# Indicators_Buttons.net
KiCad netlist of a schematic drawn in Altium Designer
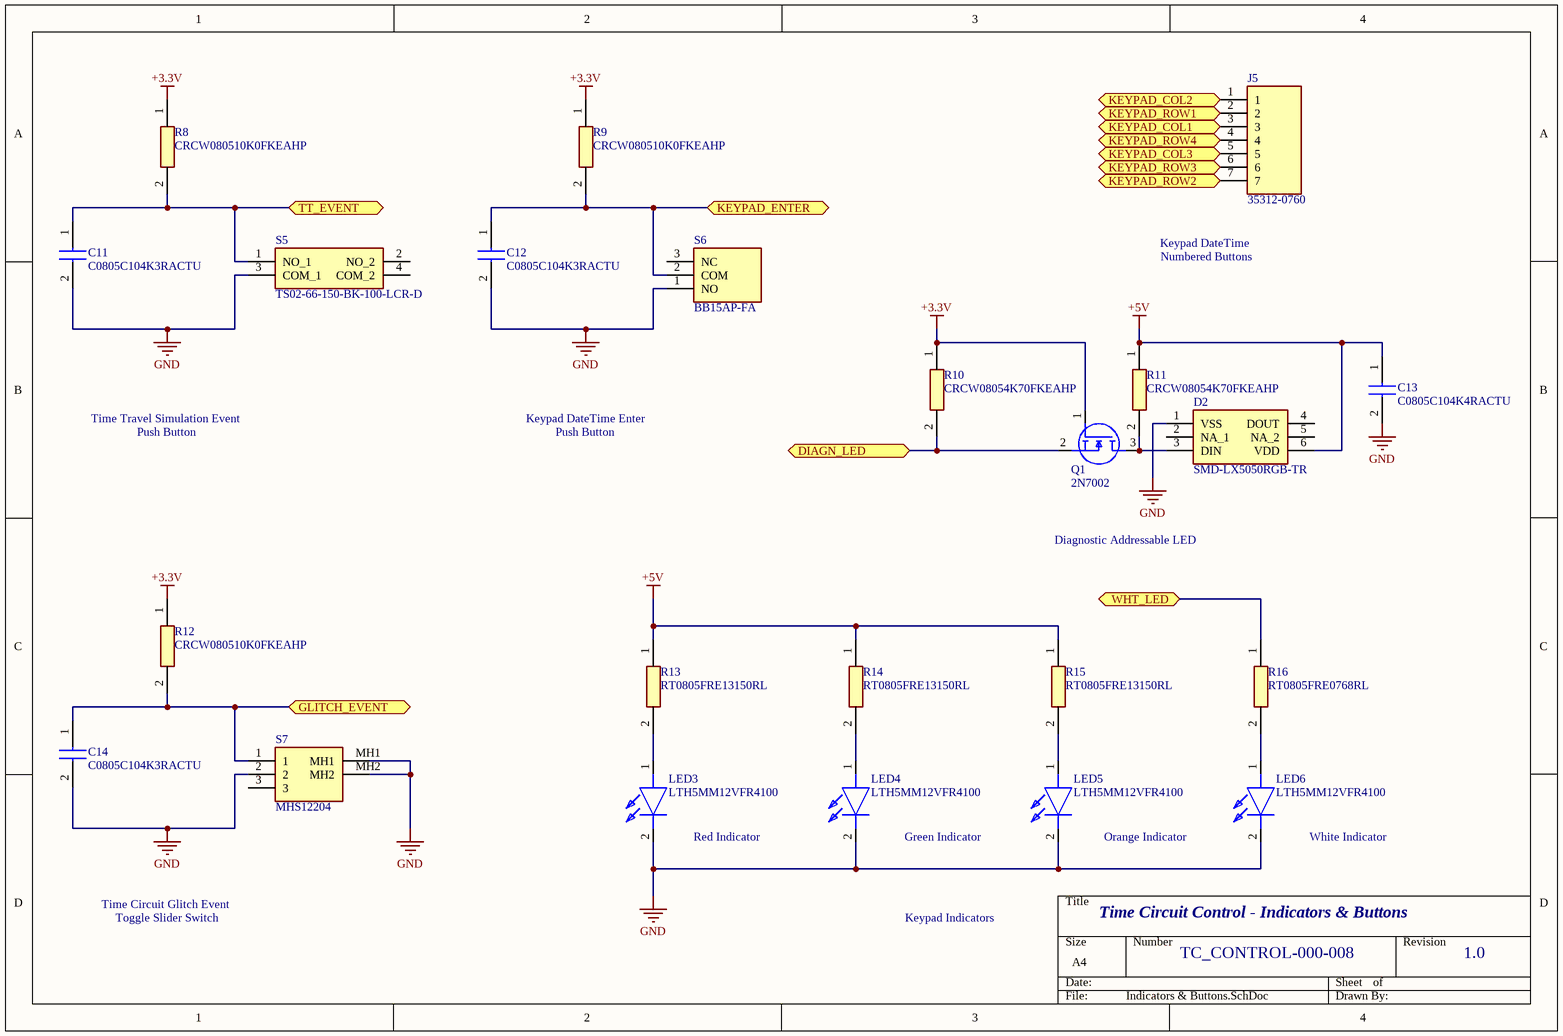
[diagram p0: Indicators & Buttons.SchDoc]

(export (version "E")
  (design (tool "Eeschema 10.0.6"))
  (components
    (comp (ref "C11")
      (value "C0805C104K3RACTU")
      (footprint "SamacSys:CAPC2012X88N")
      (description "Capacitor")
      (fields (field (name "MOUSER PART NUMBER") "80-C0805C104K3R"))
      (libsource (lib "SamacSys") (part "C0805C104K3RACTU"))
    )
    (comp (ref "C12")
      (value "C0805C104K3RACTU")
      (footprint "SamacSys:CAPC2012X88N")
      (description "Capacitor")
      (fields (field (name "MOUSER PART NUMBER") "80-C0805C104K3R"))
      (libsource (lib "SamacSys") (part "C0805C104K3RACTU"))
    )
    (comp (ref "C13")
      (value "C0805C104K4RACTU")
      (footprint "SamacSys:CAPC2012X88N")
      (description "Capacitor")
      (fields (field (name "MOUSER PART NUMBER") "80-C0805C104K4R"))
      (libsource (lib "SamacSys") (part "C0805C104K4RACTU"))
    )
    (comp (ref "C14")
      (value "C0805C104K3RACTU")
      (footprint "SamacSys:CAPC2012X88N")
      (description "Capacitor")
      (fields (field (name "MOUSER PART NUMBER") "80-C0805C104K3R"))
      (libsource (lib "SamacSys") (part "C0805C104K3RACTU"))
    )
    (comp (ref "D2")
      (value "SMD-LX5050RGB-TR")
      (footprint "SamacSys:SMDLX5050RGBTR")
      (description "Diode")
      (fields (field (name "MOUSER PART NUMBER") "696-SMDLX5050RGBTR"))
      (libsource (lib "SamacSys") (part "SMD-LX5050RGB-TR"))
    )
    (comp (ref "J5")
      (value "35312-0760")
      (footprint "SamacSys:SHDR7W64P0X250_1X7_1996X650X700P")
      (description "Connector")
      (fields (field (name "MOUSER PART NUMBER") "538-35312-0760"))
      (libsource (lib "SamacSys") (part "35312-0760"))
    )
    (comp (ref "LED3")
      (value "LTH5MM12VFR4100")
      (footprint "SamacSys:LTH5MM12VFR4100")
      (description "LED")
      (fields (field (name "MOUSER PART NUMBER") "593-LTH5MM12VFR4100"))
      (libsource (lib "SamacSys") (part "LTH5MM12VFR4100"))
    )
    (comp (ref "LED4")
      (value "LTH5MM12VFR4100")
      (footprint "SamacSys:LTH5MM12VFR4100")
      (description "LED")
      (fields (field (name "MOUSER PART NUMBER") "593-LTH5MM12VFR4100"))
      (libsource (lib "SamacSys") (part "LTH5MM12VFR4100"))
    )
    (comp (ref "LED5")
      (value "LTH5MM12VFR4100")
      (footprint "SamacSys:LTH5MM12VFR4100")
      (description "LED")
      (fields (field (name "MOUSER PART NUMBER") "593-LTH5MM12VFR4100"))
      (libsource (lib "SamacSys") (part "LTH5MM12VFR4100"))
    )
    (comp (ref "LED6")
      (value "LTH5MM12VFR4100")
      (footprint "SamacSys:LTH5MM12VFR4100")
      (description "LED")
      (fields (field (name "MOUSER PART NUMBER") "593-LTH5MM12VFR4100"))
      (libsource (lib "SamacSys") (part "LTH5MM12VFR4100"))
    )
    (comp (ref "Q1")
      (value "2N7002")
      (footprint "SamacSys:SOT96P240X120-3N")
      (description "MOSFET (N-Channel)")
      (fields (field (name "MOUSER PART NUMBER") "781-2N7002"))
      (libsource (lib "SamacSys") (part "2N7002"))
    )
    (comp (ref "R8")
      (value "CRCW080510K0FKEAHP")
      (footprint "SamacSys:RESC2012X60N")
      (description "Resistor")
      (fields (field (name "MOUSER PART NUMBER") "71-CRCW080510K0FKEAH"))
      (libsource (lib "SamacSys") (part "CRCW080510K0FKEAHP"))
    )
    (comp (ref "R9")
      (value "CRCW080510K0FKEAHP")
      (footprint "SamacSys:RESC2012X60N")
      (description "Resistor")
      (fields (field (name "MOUSER PART NUMBER") "71-CRCW080510K0FKEAH"))
      (libsource (lib "SamacSys") (part "CRCW080510K0FKEAHP"))
    )
    (comp (ref "R10")
      (value "CRCW08054K70FKEAHP")
      (footprint "SamacSys:RESC2012X50N")
      (description "Resistor")
      (fields (field (name "MOUSER PART NUMBER") "71-CRCW08054K70FKEAH"))
      (libsource (lib "SamacSys") (part "CRCW08054K70FKEAHP"))
    )
    (comp (ref "R11")
      (value "CRCW08054K70FKEAHP")
      (footprint "SamacSys:RESC2012X50N")
      (description "Resistor")
      (fields (field (name "MOUSER PART NUMBER") "71-CRCW08054K70FKEAH"))
      (libsource (lib "SamacSys") (part "CRCW08054K70FKEAHP"))
    )
    (comp (ref "R12")
      (value "CRCW080510K0FKEAHP")
      (footprint "SamacSys:RESC2012X60N")
      (description "Resistor")
      (fields (field (name "MOUSER PART NUMBER") "71-CRCW080510K0FKEAH"))
      (libsource (lib "SamacSys") (part "CRCW080510K0FKEAHP"))
    )
    (comp (ref "R13")
      (value "RT0805FRE13150RL")
      (footprint "SamacSys:RESC2012X60N")
      (description "Resistor")
      (fields (field (name "MOUSER PART NUMBER") "603-RT0805FRE13150RL"))
      (libsource (lib "*") (part "RT0805FRE13150RL"))
    )
    (comp (ref "R14")
      (value "RT0805FRE13150RL")
      (footprint "SamacSys:RESC2012X60N")
      (description "Resistor")
      (fields (field (name "MOUSER PART NUMBER") "603-RT0805FRE13150RL"))
      (libsource (lib "*") (part "RT0805FRE13150RL"))
    )
    (comp (ref "R15")
      (value "RT0805FRE13150RL")
      (footprint "SamacSys:RESC2012X60N")
      (description "Resistor")
      (fields (field (name "MOUSER PART NUMBER") "603-RT0805FRE13150RL"))
      (libsource (lib "*") (part "RT0805FRE13150RL"))
    )
    (comp (ref "R16")
      (value "RT0805FRE0768RL")
      (footprint "SamacSys:RESC2012X60N")
      (description "Resistor")
      (fields (field (name "MOUSER PART NUMBER") "603-RT0805FRE0768RL"))
      (libsource (lib "*") (part "RT0805FRE0768RL"))
    )
    (comp (ref "S5")
      (value "TS02-66-150-BK-100-LCR-D")
      (footprint "SamacSys:TS0266150BK100LCRD")
      (description "Integrated Circuit")
      (fields (field (name "MOUSER PART NUMBER") "179-TS0266150BK100LC"))
      (libsource (lib "*") (part "TS02-66-150-BK-100-LCR-D"))
    )
    (comp (ref "S6")
      (value "BB15AP-FA")
      (footprint "SamacSys:BB15APFA")
      (description "Switch")
      (fields (field (name "MOUSER PART NUMBER") "633-BB15AP-FA"))
      (libsource (lib "SamacSys") (part "BB15AP-FA"))
    )
    (comp (ref "S7")
      (value "MHS12204")
      (footprint "SamacSys:MHS12204")
      (description "Switch")
      (fields (field (name "MOUSER PART NUMBER") "506-MHS12204"))
      (libsource (lib "SamacSys") (part "MHS12204"))
    )
  )
  (nets
    (net (code "1") (name "+3.3V") (class "Default")
      (node (ref "Q1") (pin "1") (pinfunction "G_1") (pintype "passive"))
      (node (ref "R10") (pin "1") (pinfunction "1_1") (pintype "passive"))
      (node (ref "R12") (pin "1") (pinfunction "1_1") (pintype "passive"))
      (node (ref "R8") (pin "1") (pinfunction "1_1") (pintype "passive"))
      (node (ref "R9") (pin "1") (pinfunction "1_1") (pintype "passive"))
    )
    (net (code "2") (name "+5V") (class "Default")
      (node (ref "C13") (pin "1") (pinfunction "1_1") (pintype "passive"))
      (node (ref "D2") (pin "6") (pinfunction "VDD_6") (pintype "passive"))
      (node (ref "R11") (pin "1") (pinfunction "1_1") (pintype "passive"))
      (node (ref "R13") (pin "1") (pinfunction "1_1") (pintype "passive"))
      (node (ref "R14") (pin "1") (pinfunction "1_1") (pintype "passive"))
      (node (ref "R15") (pin "1") (pinfunction "1_1") (pintype "passive"))
    )
    (net (code "3") (name "/DIAGN_LED") (class "Default")
      (node (ref "Q1") (pin "2") (pinfunction "S_2") (pintype "passive"))
      (node (ref "R10") (pin "2") (pinfunction "2_2") (pintype "passive"))
    )
    (net (code "4") (name "/GLITCH_EVENT") (class "Default")
      (node (ref "C14") (pin "1") (pinfunction "1_1") (pintype "passive"))
      (node (ref "R12") (pin "2") (pinfunction "2_2") (pintype "passive"))
      (node (ref "S7") (pin "1") (pinfunction "1_1") (pintype "passive"))
    )
    (net (code "5") (name "/KEYPAD_COL1") (class "Default")
      (node (ref "J5") (pin "3") (pinfunction "3_3") (pintype "passive"))
    )
    (net (code "6") (name "/KEYPAD_COL2") (class "Default")
      (node (ref "J5") (pin "1") (pinfunction "1_1") (pintype "passive"))
    )
    (net (code "7") (name "/KEYPAD_COL3") (class "Default")
      (node (ref "J5") (pin "5") (pinfunction "5_5") (pintype "passive"))
    )
    (net (code "8") (name "/KEYPAD_ENTER") (class "Default")
      (node (ref "C12") (pin "1") (pinfunction "1_1") (pintype "passive"))
      (node (ref "R9") (pin "2") (pinfunction "2_2") (pintype "passive"))
      (node (ref "S6") (pin "2") (pinfunction "COM_2") (pintype "passive"))
    )
    (net (code "9") (name "/KEYPAD_ROW1") (class "Default")
      (node (ref "J5") (pin "2") (pinfunction "2_2") (pintype "passive"))
    )
    (net (code "10") (name "/KEYPAD_ROW2") (class "Default")
      (node (ref "J5") (pin "7") (pinfunction "7_7") (pintype "passive"))
    )
    (net (code "11") (name "/KEYPAD_ROW3") (class "Default")
      (node (ref "J5") (pin "6") (pinfunction "6_6") (pintype "passive"))
    )
    (net (code "12") (name "/KEYPAD_ROW4") (class "Default")
      (node (ref "J5") (pin "4") (pinfunction "4_4") (pintype "passive"))
    )
    (net (code "13") (name "/TT_EVENT") (class "Default")
      (node (ref "C11") (pin "1") (pinfunction "1_1") (pintype "passive"))
      (node (ref "R8") (pin "2") (pinfunction "2_2") (pintype "passive"))
      (node (ref "S5") (pin "1") (pinfunction "NO_1_1") (pintype "passive"))
    )
    (net (code "14") (name "/WHT_LED") (class "Default")
      (node (ref "R16") (pin "1") (pinfunction "1_1") (pintype "passive"))
    )
    (net (code "15") (name "GND") (class "Default")
      (node (ref "C11") (pin "2") (pinfunction "2_2") (pintype "passive"))
      (node (ref "C12") (pin "2") (pinfunction "2_2") (pintype "passive"))
      (node (ref "C13") (pin "2") (pinfunction "2_2") (pintype "passive"))
      (node (ref "C14") (pin "2") (pinfunction "2_2") (pintype "passive"))
      (node (ref "D2") (pin "1") (pinfunction "VSS_1") (pintype "passive"))
      (node (ref "LED3") (pin "2") (pinfunction "K_2") (pintype "passive"))
      (node (ref "LED4") (pin "2") (pinfunction "K_2") (pintype "passive"))
      (node (ref "LED5") (pin "2") (pinfunction "K_2") (pintype "passive"))
      (node (ref "LED6") (pin "2") (pinfunction "K_2") (pintype "passive"))
      (node (ref "S5") (pin "3") (pinfunction "COM_1_3") (pintype "passive"))
      (node (ref "S6") (pin "1") (pinfunction "NO_1") (pintype "passive"))
      (node (ref "S7") (pin "2") (pinfunction "2_2") (pintype "passive"))
      (node (ref "S7") (pin "MH1") (pinfunction "MH1_MH1") (pintype "passive"))
      (node (ref "S7") (pin "MH2") (pinfunction "MH2_MH2") (pintype "passive"))
    )
    (net (code "16") (name "Net-(D2-DIN)") (class "Default")
      (node (ref "D2") (pin "3") (pinfunction "DIN_3") (pintype "passive"))
      (node (ref "Q1") (pin "3") (pinfunction "D_3") (pintype "passive"))
      (node (ref "R11") (pin "2") (pinfunction "2_2") (pintype "passive"))
    )
    (net (code "17") (name "Net-(LED3-A)") (class "Default")
      (node (ref "LED3") (pin "1") (pinfunction "A_1") (pintype "passive"))
      (node (ref "R13") (pin "2") (pinfunction "2_2") (pintype "passive"))
    )
    (net (code "18") (name "Net-(LED4-A)") (class "Default")
      (node (ref "LED4") (pin "1") (pinfunction "A_1") (pintype "passive"))
      (node (ref "R14") (pin "2") (pinfunction "2_2") (pintype "passive"))
    )
    (net (code "19") (name "Net-(LED5-A)") (class "Default")
      (node (ref "LED5") (pin "1") (pinfunction "A_1") (pintype "passive"))
      (node (ref "R15") (pin "2") (pinfunction "2_2") (pintype "passive"))
    )
    (net (code "20") (name "Net-(LED6-A)") (class "Default")
      (node (ref "LED6") (pin "1") (pinfunction "A_1") (pintype "passive"))
      (node (ref "R16") (pin "2") (pinfunction "2_2") (pintype "passive"))
    )
    (net (code "21") (name "unconnected-(D2-DOUT-Pad4)") (class "Default")
      (node (ref "D2") (pin "4") (pinfunction "DOUT_4") (pintype "passive"))
    )
    (net (code "22") (name "unconnected-(D2-NA_1-Pad2)") (class "Default")
      (node (ref "D2") (pin "2") (pinfunction "NA_1_2") (pintype "passive"))
    )
    (net (code "23") (name "unconnected-(D2-NA_2-Pad5)") (class "Default")
      (node (ref "D2") (pin "5") (pinfunction "NA_2_5") (pintype "passive"))
    )
    (net (code "24") (name "unconnected-(S5-COM_2-Pad4)") (class "Default")
      (node (ref "S5") (pin "4") (pinfunction "COM_2_4") (pintype "passive"))
    )
    (net (code "25") (name "unconnected-(S5-NO_2-Pad2)") (class "Default")
      (node (ref "S5") (pin "2") (pinfunction "NO_2_2") (pintype "passive"))
    )
    (net (code "26") (name "unconnected-(S6-NC-Pad3)") (class "Default")
      (node (ref "S6") (pin "3") (pinfunction "NC_3") (pintype "passive"))
    )
    (net (code "27") (name "unconnected-(S7-Pad3)") (class "Default")
      (node (ref "S7") (pin "3") (pinfunction "3_3") (pintype "passive"))
    )
  )
)
